# rfm98pw-wing.net
KiCad netlist of a schematic drawn in EAGLE
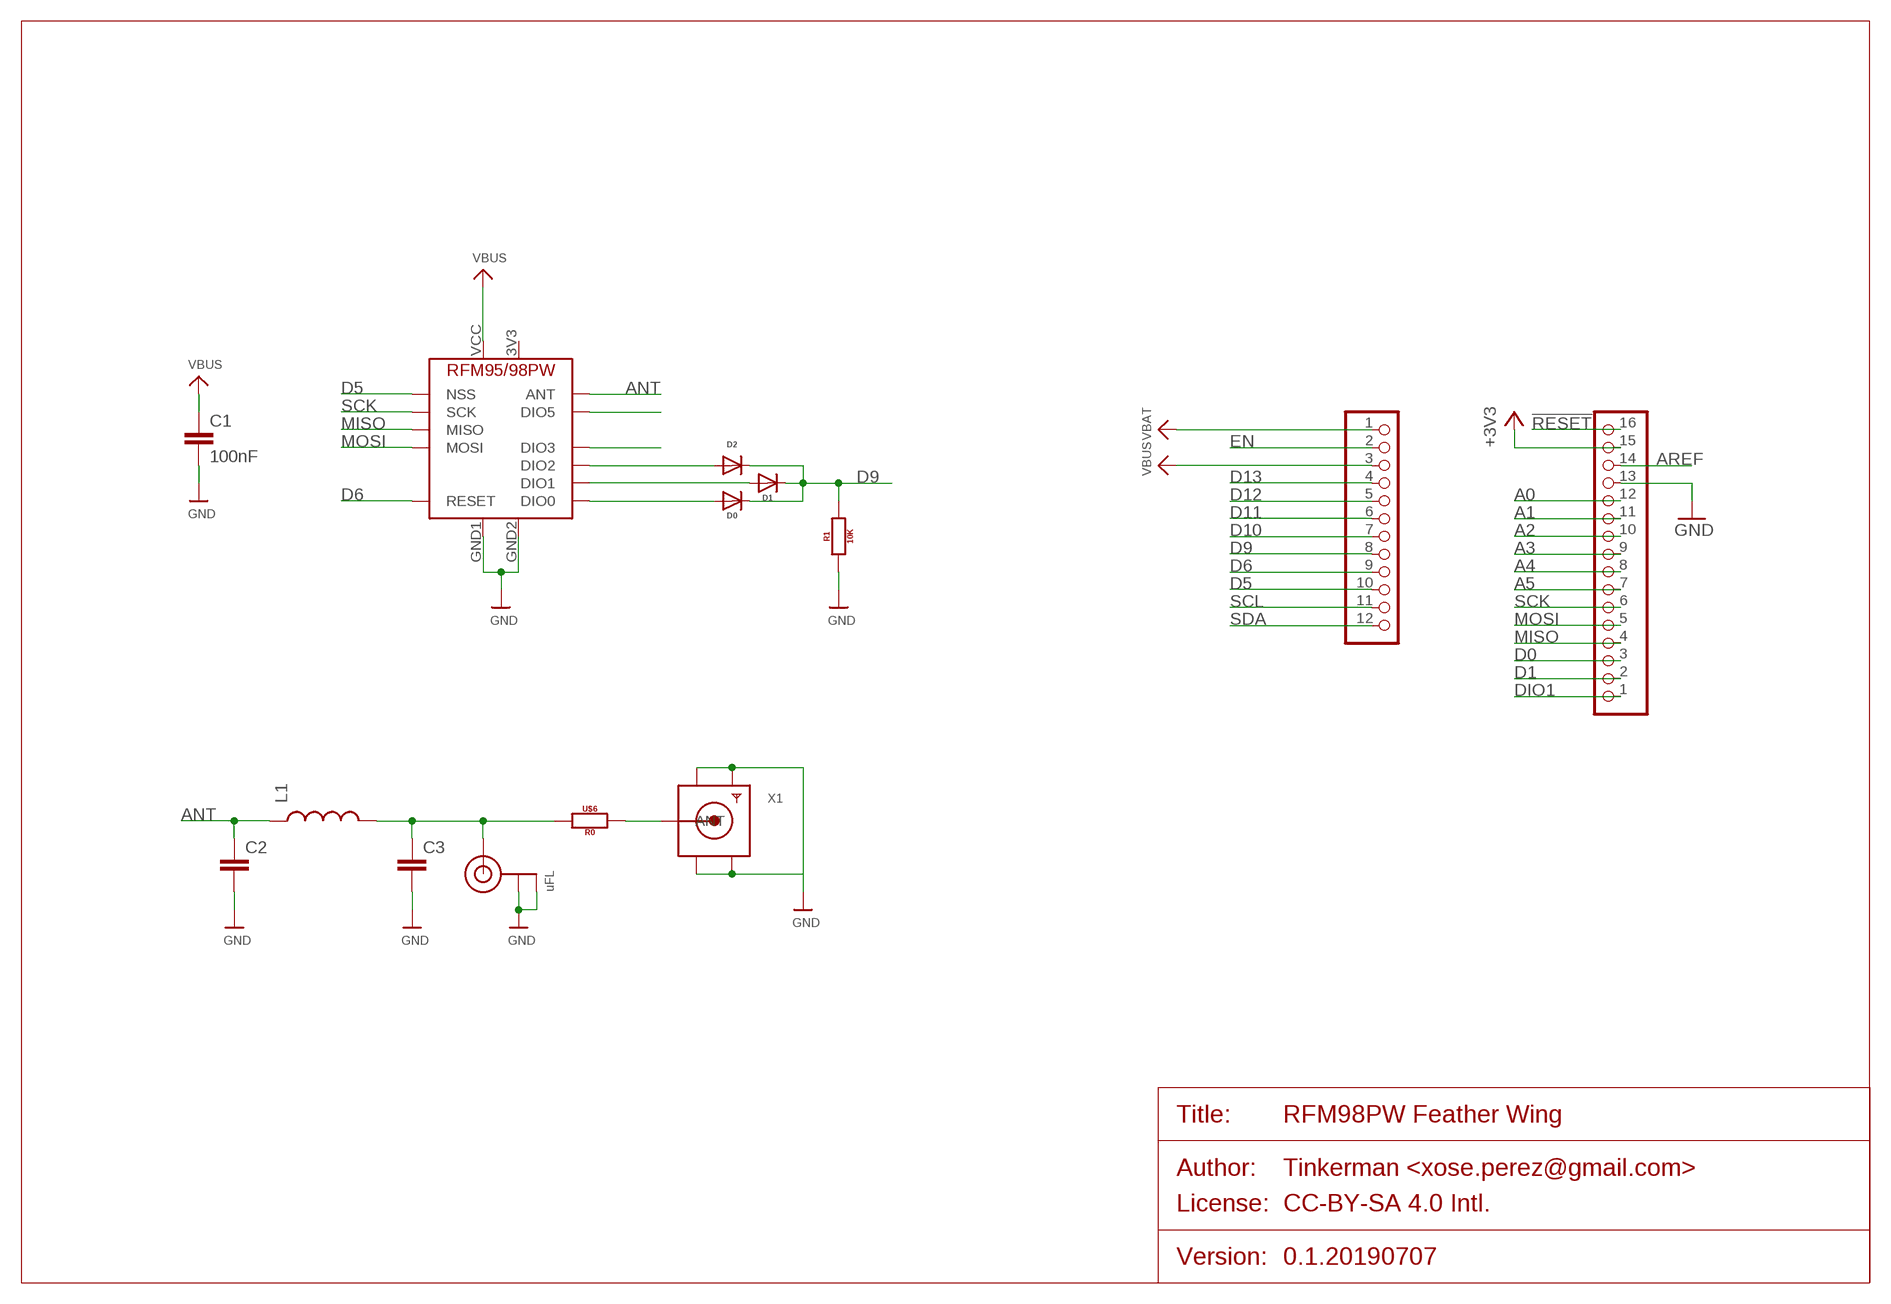
[diagram p0: schematic, sheet 1]

(export (version "E")
  (design (tool "Eeschema 10.0.6"))
  (components
    (comp (ref "C1")
      (value "100nF")
      (footprint "eagle-import:C0805K")
      (libsource (lib "eagle-import") (part "C-EUC0805K"))
    )
    (comp (ref "C2")
      (value "C-EUC0805K")
      (footprint "eagle-import:C0805K")
      (libsource (lib "eagle-import") (part "C-EUC0805K"))
    )
    (comp (ref "C3")
      (value "C-EUC0805K")
      (footprint "eagle-import:C0805K")
      (libsource (lib "eagle-import") (part "C-EUC0805K"))
    )
    (comp (ref "D0")
      (value "DIODE-SMD")
      (footprint "eagle-import:0805_DIODE")
      (libsource (lib "eagle-import") (part "DIODE-SMD"))
    )
    (comp (ref "D1")
      (value "DIODE-SMD")
      (footprint "eagle-import:0805_DIODE")
      (libsource (lib "eagle-import") (part "DIODE-SMD"))
    )
    (comp (ref "D2")
      (value "DIODE-SMD")
      (footprint "eagle-import:0805_DIODE")
      (libsource (lib "eagle-import") (part "DIODE-SMD"))
    )
    (comp (ref "JP1")
      (value "HEADER-1X16ROUND")
      (footprint "eagle-import:1X16_ROUND")
      (libsource (lib "eagle-import") (part "HEADER-1X16ROUND"))
    )
    (comp (ref "JP3")
      (value "HEADER-1X12")
      (footprint "eagle-import:1X12_ROUND")
      (libsource (lib "eagle-import") (part "HEADER-1X12"))
    )
    (comp (ref "L1")
      (value "INDUCTOR-SPARKFUN0805")
      (footprint "eagle-import:0805")
      (libsource (lib "eagle-import") (part "INDUCTOR-SPARKFUN0805"))
    )
    (comp (ref "R1")
      (value "10K")
      (footprint "eagle-import:0805")
      (libsource (lib "eagle-import") (part "RESISTOR0805"))
    )
    (comp (ref "U$6")
      (value "R0")
      (footprint "eagle-import:0805")
      (libsource (lib "eagle-import") (part "RESISTOR0805"))
    )
    (comp (ref "U$24")
      (value "RFM95PW-RFM98PW")
      (footprint "eagle-import:RFM95PW-RFM98PW")
      (libsource (lib "eagle-import") (part "RFM95PW-RFM98PW"))
    )
    (comp (ref "X1")
      (value "SMACONNECTOR_EDGE")
      (footprint "eagle-import:SMA_EDGELAUNCH")
      (libsource (lib "eagle-import") (part "SMACONNECTOR_EDGE"))
    )
    (comp (ref "X4")
      (value "uFL")
      (footprint "eagle-import:U.FL")
      (libsource (lib "eagle-import") (part "ANTENNA_U.FL"))
    )
  )
  (nets
    (net (code "1") (name "+3V3") (class "Default")
      (node (ref "JP1") (pin "15") (pinfunction "15_15") (pintype "passive"))
    )
    (net (code "2") (name "/3V3") (class "Default")
      (node (ref "U$24") (pin "3V3") (pinfunction "3V3_3V3") (pintype "power_in"))
    )
    (net (code "3") (name "/A0") (class "Default")
      (node (ref "JP1") (pin "12") (pinfunction "12_12") (pintype "passive"))
    )
    (net (code "4") (name "/A1") (class "Default")
      (node (ref "JP1") (pin "11") (pinfunction "11_11") (pintype "passive"))
    )
    (net (code "5") (name "/A2") (class "Default")
      (node (ref "JP1") (pin "10") (pinfunction "10_10") (pintype "passive"))
    )
    (net (code "6") (name "/A3") (class "Default")
      (node (ref "JP1") (pin "9") (pinfunction "9_9") (pintype "passive"))
    )
    (net (code "7") (name "/A4") (class "Default")
      (node (ref "JP1") (pin "8") (pinfunction "8_8") (pintype "passive"))
    )
    (net (code "8") (name "/A5") (class "Default")
      (node (ref "JP1") (pin "7") (pinfunction "7_7") (pintype "passive"))
    )
    (net (code "9") (name "/ANT") (class "Default")
      (node (ref "C2") (pin "1") (pinfunction "1_1") (pintype "passive"))
      (node (ref "L1") (pin "1") (pinfunction "1_1") (pintype "passive"))
      (node (ref "U$24") (pin "ANT") (pinfunction "ANT_ANT") (pintype "passive"))
    )
    (net (code "10") (name "/AREF") (class "Default")
      (node (ref "JP1") (pin "14") (pinfunction "14_14") (pintype "passive"))
    )
    (net (code "11") (name "/D0") (class "Default")
      (node (ref "JP1") (pin "3") (pinfunction "3_3") (pintype "passive"))
    )
    (net (code "12") (name "/D1") (class "Default")
      (node (ref "JP1") (pin "2") (pinfunction "2_2") (pintype "passive"))
    )
    (net (code "13") (name "/D5") (class "Default")
      (node (ref "JP3") (pin "10") (pinfunction "10_10") (pintype "passive"))
      (node (ref "U$24") (pin "NSS") (pinfunction "NSS_NSS") (pintype "input"))
    )
    (net (code "14") (name "/D6") (class "Default")
      (node (ref "JP3") (pin "9") (pinfunction "9_9") (pintype "passive"))
      (node (ref "U$24") (pin "RESET") (pinfunction "RESET_RESET") (pintype "input"))
    )
    (net (code "15") (name "/D9") (class "Default")
      (node (ref "D0") (pin "C") (pinfunction "C_C") (pintype "passive"))
      (node (ref "D1") (pin "C") (pinfunction "C_C") (pintype "passive"))
      (node (ref "D2") (pin "C") (pinfunction "C_C") (pintype "passive"))
      (node (ref "JP3") (pin "8") (pinfunction "8_8") (pintype "passive"))
      (node (ref "R1") (pin "2") (pinfunction "2_2") (pintype "passive"))
    )
    (net (code "16") (name "/D10") (class "Default")
      (node (ref "JP3") (pin "7") (pinfunction "7_7") (pintype "passive"))
    )
    (net (code "17") (name "/D11") (class "Default")
      (node (ref "JP3") (pin "6") (pinfunction "6_6") (pintype "passive"))
    )
    (net (code "18") (name "/D12") (class "Default")
      (node (ref "JP3") (pin "5") (pinfunction "5_5") (pintype "passive"))
    )
    (net (code "19") (name "/D13") (class "Default")
      (node (ref "JP3") (pin "4") (pinfunction "4_4") (pintype "passive"))
    )
    (net (code "20") (name "/DIO1") (class "Default")
      (node (ref "JP1") (pin "1") (pinfunction "1_1") (pintype "passive"))
    )
    (net (code "21") (name "/EN") (class "Default")
      (node (ref "JP3") (pin "2") (pinfunction "2_2") (pintype "passive"))
    )
    (net (code "22") (name "/MISO") (class "Default")
      (node (ref "JP1") (pin "4") (pinfunction "4_4") (pintype "passive"))
      (node (ref "U$24") (pin "MISO") (pinfunction "MISO_MISO") (pintype "output"))
    )
    (net (code "23") (name "/MOSI") (class "Default")
      (node (ref "JP1") (pin "5") (pinfunction "5_5") (pintype "passive"))
      (node (ref "U$24") (pin "MOSI") (pinfunction "MOSI_MOSI") (pintype "input"))
    )
    (net (code "24") (name "/SCK") (class "Default")
      (node (ref "JP1") (pin "6") (pinfunction "6_6") (pintype "passive"))
      (node (ref "U$24") (pin "SCK") (pinfunction "SCK_SCK") (pintype "input"))
    )
    (net (code "25") (name "/SCL") (class "Default")
      (node (ref "JP3") (pin "11") (pinfunction "11_11") (pintype "passive"))
    )
    (net (code "26") (name "/SDA") (class "Default")
      (node (ref "JP3") (pin "12") (pinfunction "12_12") (pintype "passive"))
    )
    (net (code "27") (name "/~{RESET}") (class "Default")
      (node (ref "JP1") (pin "16") (pinfunction "16_16") (pintype "passive"))
    )
    (net (code "28") (name "GND") (class "Default")
      (node (ref "C1") (pin "2") (pinfunction "2_2") (pintype "passive"))
      (node (ref "C2") (pin "2") (pinfunction "2_2") (pintype "passive"))
      (node (ref "C3") (pin "2") (pinfunction "2_2") (pintype "passive"))
      (node (ref "JP1") (pin "13") (pinfunction "13_13") (pintype "passive"))
      (node (ref "R1") (pin "1") (pinfunction "1_1") (pintype "passive"))
      (node (ref "U$24") (pin "GND1") (pinfunction "GND1_GND1") (pintype "power_in"))
      (node (ref "U$24") (pin "GND2") (pinfunction "GND2_GND2") (pintype "power_in"))
      (node (ref "X1") (pin "GND@1") (pinfunction "GND4_GND@1") (pintype "power_in"))
      (node (ref "X1") (pin "GND@2") (pinfunction "GND3_GND@2") (pintype "power_in"))
      (node (ref "X1") (pin "GND@3") (pinfunction "GND2_GND@3") (pintype "power_in"))
      (node (ref "X1") (pin "GND@4") (pinfunction "GND1_GND@4") (pintype "power_in"))
      (node (ref "X4") (pin "1") (pinfunction "GND_1") (pintype "passive"))
      (node (ref "X4") (pin "2") (pinfunction "GND_2") (pintype "passive"))
    )
    (net (code "29") (name "Net-(D0-PadA)") (class "Default")
      (node (ref "D0") (pin "A") (pinfunction "A_A") (pintype "passive"))
      (node (ref "U$24") (pin "DIO0") (pinfunction "DIO0_DIO0") (pintype "bidirectional"))
    )
    (net (code "30") (name "Net-(D1-PadA)") (class "Default")
      (node (ref "D1") (pin "A") (pinfunction "A_A") (pintype "passive"))
      (node (ref "U$24") (pin "DIO1") (pinfunction "DIO1_DIO1") (pintype "bidirectional"))
    )
    (net (code "31") (name "Net-(D2-PadA)") (class "Default")
      (node (ref "D2") (pin "A") (pinfunction "A_A") (pintype "passive"))
      (node (ref "U$24") (pin "DIO2") (pinfunction "DIO2_DIO2") (pintype "bidirectional"))
    )
    (net (code "32") (name "Net-(X1-ANT)") (class "Default")
      (node (ref "U$6") (pin "2") (pinfunction "2_2") (pintype "passive"))
      (node (ref "X1") (pin "P") (pinfunction "ANT_P") (pintype "bidirectional"))
    )
    (net (code "33") (name "Net-(X4-SIGNAL)") (class "Default")
      (node (ref "C3") (pin "1") (pinfunction "1_1") (pintype "passive"))
      (node (ref "L1") (pin "2") (pinfunction "2_2") (pintype "passive"))
      (node (ref "U$6") (pin "1") (pinfunction "1_1") (pintype "passive"))
      (node (ref "X4") (pin "3") (pinfunction "SIGNAL_3") (pintype "passive"))
    )
    (net (code "34") (name "VBAT") (class "Default")
      (node (ref "JP3") (pin "1") (pinfunction "1_1") (pintype "passive"))
    )
    (net (code "35") (name "VBUS") (class "Default")
      (node (ref "C1") (pin "1") (pinfunction "1_1") (pintype "passive"))
      (node (ref "JP3") (pin "3") (pinfunction "3_3") (pintype "passive"))
      (node (ref "U$24") (pin "VCC") (pinfunction "VCC_VCC") (pintype "power_in"))
    )
    (net (code "36") (name "unconnected-(U$24-PadDIO3)") (class "Default")
      (node (ref "U$24") (pin "DIO3") (pinfunction "DIO3_DIO3") (pintype "bidirectional"))
    )
    (net (code "37") (name "unconnected-(U$24-PadDIO5)") (class "Default")
      (node (ref "U$24") (pin "DIO5") (pinfunction "DIO5_DIO5") (pintype "bidirectional"))
    )
  )
)
